# VCNL4040_IR_Finger_Sensor_Production.net
KiCad netlist of a schematic drawn in EAGLE
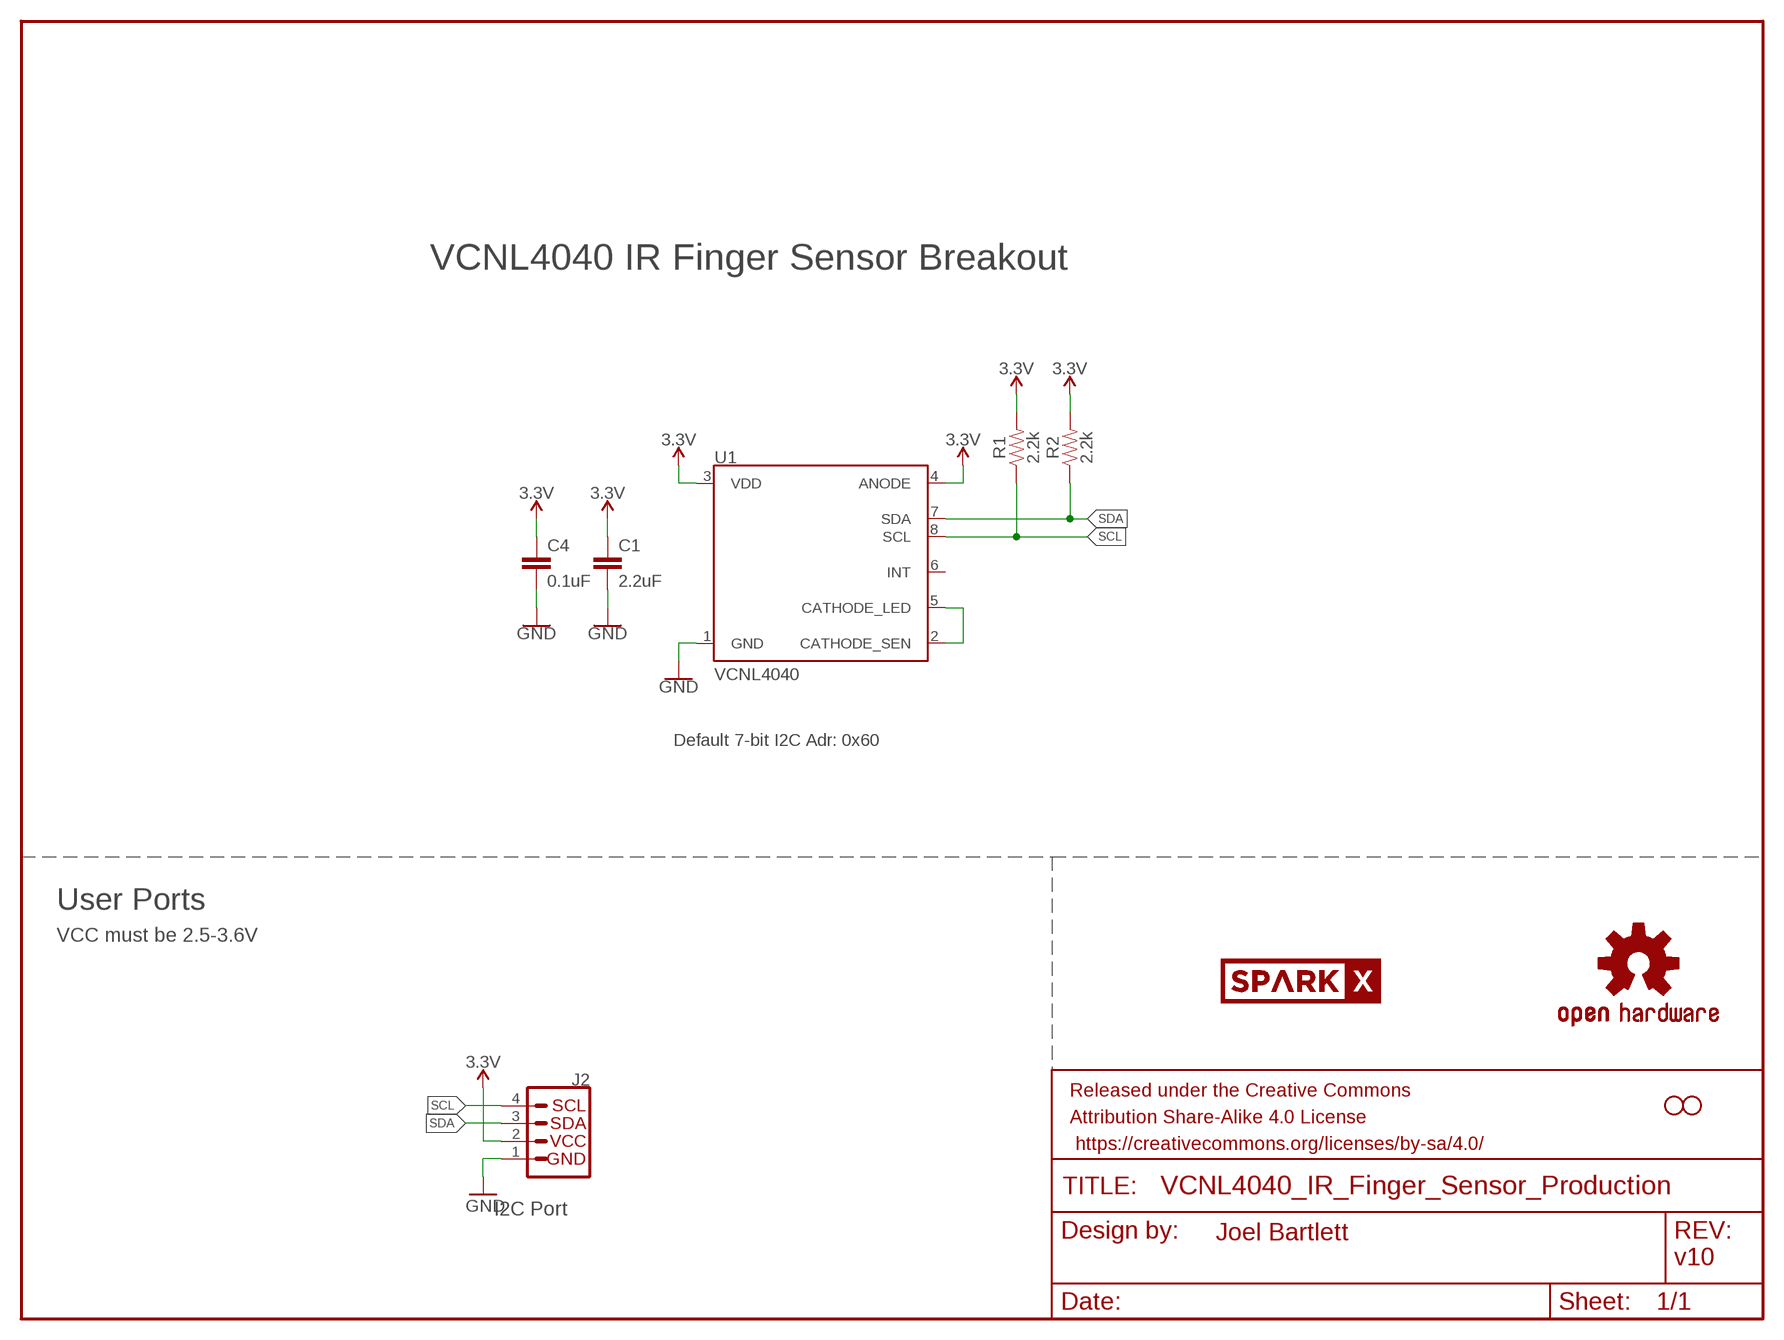
[diagram p0: schematic, sheet 1]

(export (version "E")
  (design (tool "Eeschema 10.0.6"))
  (components
    (comp (ref "C1")
      (value "2.2uF")
      (footprint "eagle-import:0603")
      (libsource (lib "eagle-import") (part "2.2UF-0603-10V-20%"))
    )
    (comp (ref "C4")
      (value "0.1uF")
      (footprint "eagle-import:0603")
      (libsource (lib "eagle-import") (part "0.1UF-0603-25V-(+80/-20%)"))
    )
    (comp (ref "FRAME2")
      (value "FRAME-LETTER")
      (footprint "eagle-import:CREATIVE_COMMONS")
      (libsource (lib "eagle-import") (part "FRAME-LETTER"))
    )
    (comp (ref "J2")
      (value "I2C_STANDARDJS-1MM")
      (footprint "eagle-import:1X04_1MM_RA")
      (libsource (lib "eagle-import") (part "I2C_STANDARDJS-1MM"))
    )
    (comp (ref "R1")
      (value "2.2k")
      (footprint "eagle-import:0603")
      (libsource (lib "eagle-import") (part "2.2KOHM-0603-1/10W-1%"))
    )
    (comp (ref "R2")
      (value "2.2k")
      (footprint "eagle-import:0603")
      (libsource (lib "eagle-import") (part "2.2KOHM-0603-1/10W-1%"))
    )
    (comp (ref "U$1")
      (value "OSHW-LOGOS")
      (footprint "eagle-import:OSHW-LOGO-S")
      (libsource (lib "eagle-import") (part "OSHW-LOGOS"))
    )
    (comp (ref "U$2")
      (value "SPARKX-LOGO3")
      (footprint "eagle-import:SPARKX-SMALL")
      (libsource (lib "eagle-import") (part "SPARKX-LOGO3"))
    )
    (comp (ref "U$3")
      (value "STAND-OFF")
      (footprint "eagle-import:STAND-OFF-#2")
      (libsource (lib "eagle-import") (part "STAND-OFF"))
    )
    (comp (ref "U$4")
      (value "STAND-OFF")
      (footprint "eagle-import:STAND-OFF-#2")
      (libsource (lib "eagle-import") (part "STAND-OFF"))
    )
    (comp (ref "U1")
      (value "VCNL4040")
      (footprint "eagle-import:VCNL4040")
      (libsource (lib "eagle-import") (part "VCNL4040"))
    )
  )
  (nets
    (net (code "1") (name "3.3V") (class "Default")
      (node (ref "C1") (pin "1") (pinfunction "1_1") (pintype "passive"))
      (node (ref "C4") (pin "1") (pinfunction "1_1") (pintype "passive"))
      (node (ref "J2") (pin "2") (pinfunction "VCC_2") (pintype "power_in"))
      (node (ref "R1") (pin "2") (pinfunction "2_2") (pintype "passive"))
      (node (ref "R2") (pin "2") (pinfunction "2_2") (pintype "passive"))
      (node (ref "U1") (pin "3") (pinfunction "VDD_3") (pintype "bidirectional"))
      (node (ref "U1") (pin "4") (pinfunction "ANODE_4") (pintype "bidirectional"))
    )
    (net (code "2") (name "GND") (class "Default")
      (node (ref "C1") (pin "2") (pinfunction "2_2") (pintype "passive"))
      (node (ref "C4") (pin "2") (pinfunction "2_2") (pintype "passive"))
      (node (ref "J2") (pin "1") (pinfunction "GND_1") (pintype "power_in"))
      (node (ref "U1") (pin "1") (pinfunction "GND_1") (pintype "bidirectional"))
    )
    (net (code "3") (name "Net-(U1-CATHODE_LED)") (class "Default")
      (node (ref "U1") (pin "2") (pinfunction "CATHODE_SEN_2") (pintype "bidirectional"))
      (node (ref "U1") (pin "5") (pinfunction "CATHODE_LED_5") (pintype "bidirectional"))
    )
    (net (code "4") (name "SCL") (class "Default")
      (node (ref "J2") (pin "4") (pinfunction "SCL_4") (pintype "passive"))
      (node (ref "R1") (pin "1") (pinfunction "1_1") (pintype "passive"))
      (node (ref "U1") (pin "8") (pinfunction "SCL_8") (pintype "bidirectional"))
    )
    (net (code "5") (name "SDA") (class "Default")
      (node (ref "J2") (pin "3") (pinfunction "SDA_3") (pintype "passive"))
      (node (ref "R2") (pin "1") (pinfunction "1_1") (pintype "passive"))
      (node (ref "U1") (pin "7") (pinfunction "SDA_7") (pintype "bidirectional"))
    )
    (net (code "6") (name "unconnected-(U1-INT-Pad6)") (class "Default")
      (node (ref "U1") (pin "6") (pinfunction "INT_6") (pintype "bidirectional"))
    )
  )
)
